# RP2350_Power.net
KiCad netlist of a schematic drawn in Altium Designer
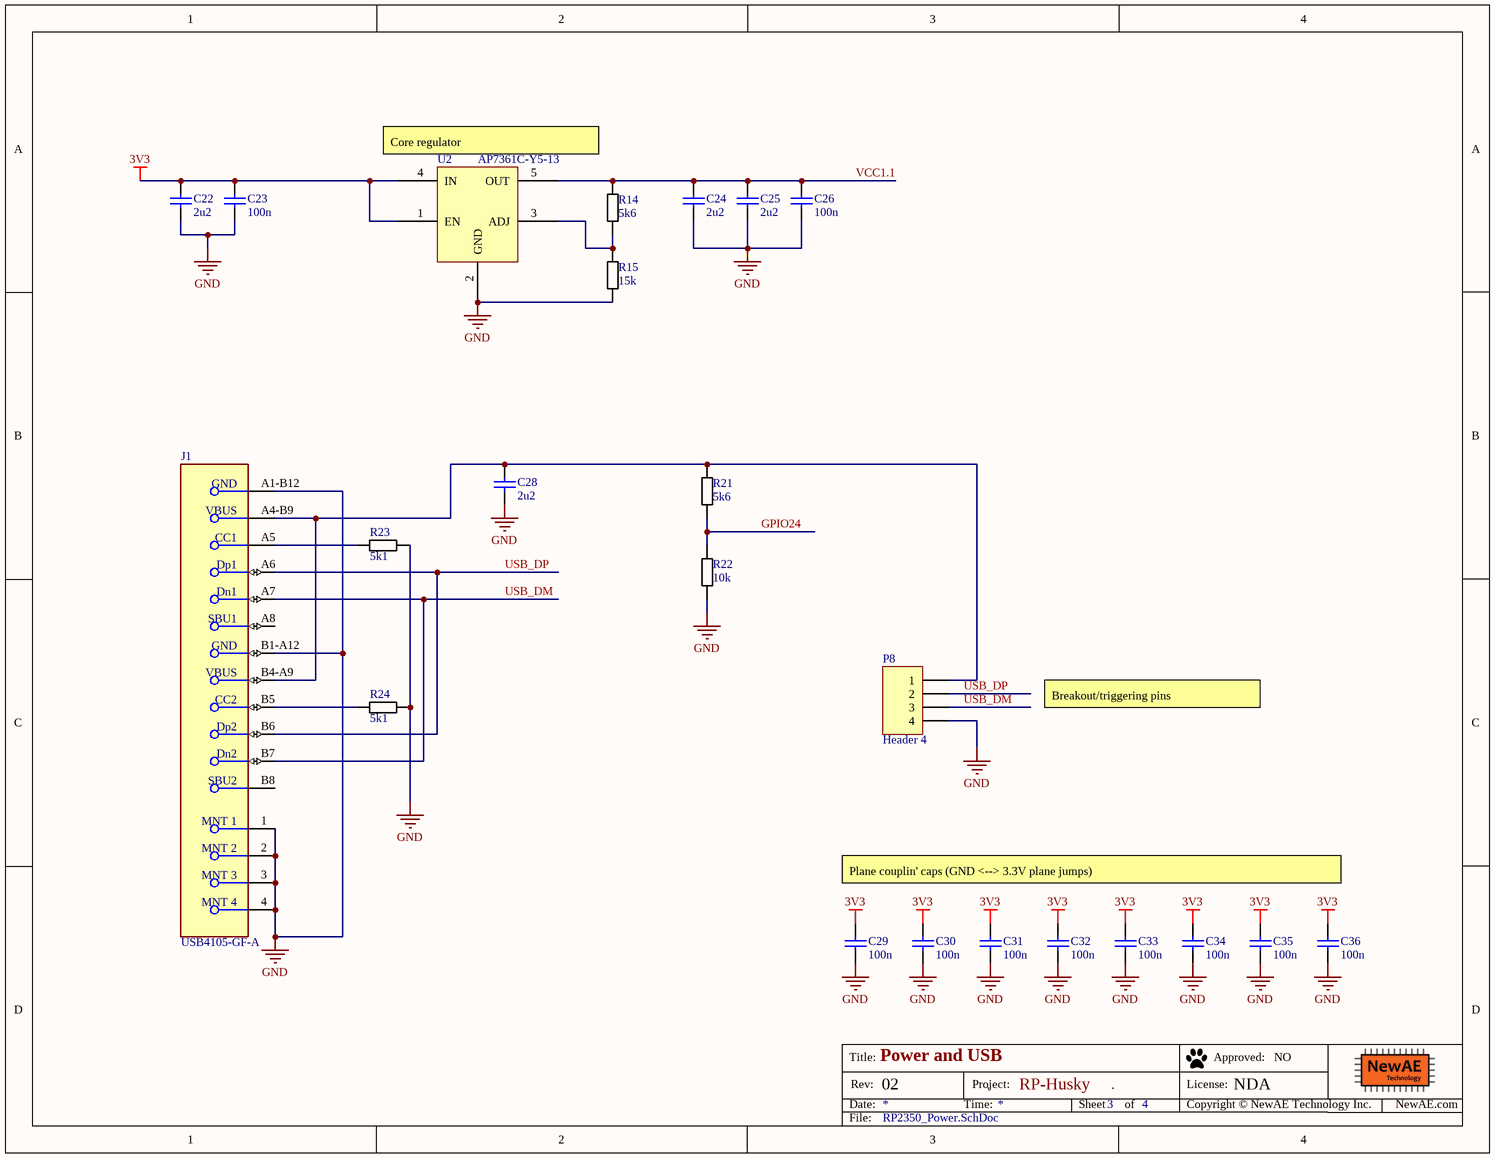
[diagram p0: RP2350_Power.SchDoc]

(export (version "E")
  (design (tool "Eeschema 10.0.6"))
  (components
    (comp (ref "C22")
      (value "2u2")
      (footprint "CAPC0603_M")
      (description "2u2, 0603")
      (fields (field (name "PART NUMBER") "CCHIP-2u2-0603"))
      (libsource (lib "NewAE_AltiumLib") (part "CAP"))
    )
    (comp (ref "C23")
      (value "100n")
      (footprint "CAPC0402_M")
      (description "100n, 0402")
      (fields (field (name "PART NUMBER") "CCHIP-100n-0402"))
      (libsource (lib "NewAE_AltiumLib") (part "CAP"))
    )
    (comp (ref "C24")
      (value "2u2")
      (footprint "CAPC0603_M")
      (description "2u2, 0603")
      (fields (field (name "PART NUMBER") "CCHIP-2u2-0603"))
      (libsource (lib "NewAE_AltiumLib") (part "CAP"))
    )
    (comp (ref "C25")
      (value "2u2")
      (footprint "CAPC0603_M")
      (description "2u2, 0603")
      (fields (field (name "PART NUMBER") "CCHIP-2u2-0603"))
      (libsource (lib "NewAE_AltiumLib") (part "CAP"))
    )
    (comp (ref "C26")
      (value "100n")
      (footprint "CAPC0402_M")
      (description "100n, 0402")
      (fields (field (name "PART NUMBER") "CCHIP-100n-0402"))
      (libsource (lib "NewAE_AltiumLib") (part "CAP"))
    )
    (comp (ref "C28")
      (value "2u2")
      (footprint "CAPC0603_M")
      (description "2u2, 0603")
      (fields (field (name "PART NUMBER") "CCHIP-2u2-0603"))
      (libsource (lib "NewAE_AltiumLib") (part "CAP"))
    )
    (comp (ref "C29")
      (value "100n")
      (footprint "CAPC0402_M")
      (description "100n, 0402")
      (fields (field (name "PART NUMBER") "CCHIP-100n-0402"))
      (libsource (lib "NewAE_AltiumLib") (part "CAP"))
    )
    (comp (ref "C30")
      (value "100n")
      (footprint "CAPC0402_M")
      (description "100n, 0402")
      (fields (field (name "PART NUMBER") "CCHIP-100n-0402"))
      (libsource (lib "NewAE_AltiumLib") (part "CAP"))
    )
    (comp (ref "C31")
      (value "100n")
      (footprint "CAPC0402_M")
      (description "100n, 0402")
      (fields (field (name "PART NUMBER") "CCHIP-100n-0402"))
      (libsource (lib "NewAE_AltiumLib") (part "CAP"))
    )
    (comp (ref "C32")
      (value "100n")
      (footprint "CAPC0402_M")
      (description "100n, 0402")
      (fields (field (name "PART NUMBER") "CCHIP-100n-0402"))
      (libsource (lib "NewAE_AltiumLib") (part "CAP"))
    )
    (comp (ref "C33")
      (value "100n")
      (footprint "CAPC0402_M")
      (description "100n, 0402")
      (fields (field (name "PART NUMBER") "CCHIP-100n-0402"))
      (libsource (lib "NewAE_AltiumLib") (part "CAP"))
    )
    (comp (ref "C34")
      (value "100n")
      (footprint "CAPC0402_M")
      (description "100n, 0402")
      (fields (field (name "PART NUMBER") "CCHIP-100n-0402"))
      (libsource (lib "NewAE_AltiumLib") (part "CAP"))
    )
    (comp (ref "C35")
      (value "100n")
      (footprint "CAPC0402_M")
      (description "100n, 0402")
      (fields (field (name "PART NUMBER") "CCHIP-100n-0402"))
      (libsource (lib "NewAE_AltiumLib") (part "CAP"))
    )
    (comp (ref "C36")
      (value "100n")
      (footprint "CAPC0402_M")
      (description "100n, 0402")
      (fields (field (name "PART NUMBER") "CCHIP-100n-0402"))
      (libsource (lib "NewAE_AltiumLib") (part "CAP"))
    )
    (comp (ref "J1")
      (value "USB4105-GF-A")
      (footprint "FP-USB4105-GF-A-MFG")
      (description "CONN RCPT USB2.0 TYPEC 5A")
      (fields
        (field (name "MANUFACTURER") "GCT")
        (field (name "OCTOPART") "https://octopart.com/usb4105-gf-a-gct-106627878")
      )
      (libsource (lib "Altium Content Vault") (part "e7c17a616881a82b79941196b4bec10"))
    )
    (comp (ref "P8")
      (value "Header 4")
      (footprint "HDR1X4")
      (description "Header, 4-Pin")
      (fields (field (name "PUBLISHER") "Altium Limited"))
      (libsource (lib "Miscellaneous Connectors") (part "Header 4"))
    )
    (comp (ref "R14")
      (value "5k6")
      (footprint "RESC1608X55N")
      (description "5k6 res, 0603, 1%, 1/10W")
      (fields (field (name "PART NUMBER") "RCHIP-5K6-0603") (field (name "TOLERANCE") "1%"))
      (libsource (lib "") (part "RES-EU_1"))
    )
    (comp (ref "R15")
      (value "15k")
      (footprint "RESC1608X55N")
      (description "15k res, 0603, 1%, 1/10W")
      (fields (field (name "PART NUMBER") "RCHIP-15K-0603") (field (name "TOLERANCE") "1%"))
      (libsource (lib "") (part "RES-EU_1"))
    )
    (comp (ref "R21")
      (value "5k6")
      (footprint "RESC1608X55N")
      (description "5k6 res, 0603, 1%, 1/10W")
      (fields (field (name "PART NUMBER") "RCHIP-5K6-0603") (field (name "TOLERANCE") "1%"))
      (libsource (lib "") (part "RES-EU_1"))
    )
    (comp (ref "R22")
      (value "10k")
      (footprint "RESC1608X55N")
      (description "10k res, 0603, 1%, 1/10W")
      (fields (field (name "PART NUMBER") "RCHIP-10K-0603") (field (name "TOLERANCE") "1%"))
      (libsource (lib "") (part "RES-EU_1"))
    )
    (comp (ref "R23")
      (value "5k1")
      (footprint "RESC1608X55N")
      (description "5k1 res, 0603, 1%, 1/10W")
      (fields (field (name "PART NUMBER") "RCHIP-5K1-0603") (field (name "TOLERANCE") "1%"))
      (libsource (lib "NewAE_AltiumLib") (part "RES-EU"))
    )
    (comp (ref "R24")
      (value "5k1")
      (footprint "RESC1608X55N")
      (description "5k1 res, 0603, 1%, 1/10W")
      (fields (field (name "PART NUMBER") "RCHIP-5K1-0603") (field (name "TOLERANCE") "1%"))
      (libsource (lib "NewAE_AltiumLib") (part "RES-EU"))
    )
    (comp (ref "U2")
      (value "AP7361C-Y5-13")
      (footprint "SOT89-5")
      (description "Regulator, Adj, LDO, 1A")
      (libsource (lib "NewAE_AltiumLib") (part "AP7361C-Y5-13"))
    )
  )
  (nets
    (net (code "1") (name "/GPIO24") (class "Default")
      (node (ref "R21") (pin "2") (pinfunction "2_2") (pintype "passive"))
      (node (ref "R22") (pin "1") (pinfunction "1_1") (pintype "passive"))
    )
    (net (code "2") (name "/USB_DM") (class "Default")
      (node (ref "J1") (pin "A7") (pinfunction "Dn1_A7") (pintype "bidirectional"))
      (node (ref "J1") (pin "B7") (pinfunction "Dn2_B7") (pintype "bidirectional"))
      (node (ref "P8") (pin "3") (pinfunction "3_3") (pintype "passive"))
    )
    (net (code "3") (name "/USB_DP") (class "Default")
      (node (ref "J1") (pin "A6") (pinfunction "Dp1_A6") (pintype "bidirectional"))
      (node (ref "J1") (pin "B6") (pinfunction "Dp2_B6") (pintype "bidirectional"))
      (node (ref "P8") (pin "2") (pinfunction "2_2") (pintype "passive"))
    )
    (net (code "4") (name "/VCC1.1") (class "Default")
      (node (ref "C24") (pin "1") (pinfunction "1_1") (pintype "passive"))
      (node (ref "C25") (pin "1") (pinfunction "1_1") (pintype "passive"))
      (node (ref "C26") (pin "1") (pinfunction "1_1") (pintype "passive"))
      (node (ref "R14") (pin "1") (pinfunction "1_1") (pintype "passive"))
      (node (ref "U2") (pin "5") (pinfunction "OUT_5") (pintype "passive"))
    )
    (net (code "5") (name "3V3") (class "Default")
      (node (ref "C22") (pin "1") (pinfunction "1_1") (pintype "passive"))
      (node (ref "C23") (pin "1") (pinfunction "1_1") (pintype "passive"))
      (node (ref "C29") (pin "1") (pinfunction "1_1") (pintype "passive"))
      (node (ref "C30") (pin "1") (pinfunction "1_1") (pintype "passive"))
      (node (ref "C31") (pin "1") (pinfunction "1_1") (pintype "passive"))
      (node (ref "C32") (pin "1") (pinfunction "1_1") (pintype "passive"))
      (node (ref "C33") (pin "1") (pinfunction "1_1") (pintype "passive"))
      (node (ref "C34") (pin "1") (pinfunction "1_1") (pintype "passive"))
      (node (ref "C35") (pin "1") (pinfunction "1_1") (pintype "passive"))
      (node (ref "C36") (pin "1") (pinfunction "1_1") (pintype "passive"))
      (node (ref "U2") (pin "1") (pinfunction "EN_1") (pintype "passive"))
      (node (ref "U2") (pin "4") (pinfunction "IN_4") (pintype "passive"))
    )
    (net (code "6") (name "GND") (class "Default")
      (node (ref "C22") (pin "2") (pinfunction "2_2") (pintype "passive"))
      (node (ref "C23") (pin "2") (pinfunction "2_2") (pintype "passive"))
      (node (ref "C24") (pin "2") (pinfunction "2_2") (pintype "passive"))
      (node (ref "C25") (pin "2") (pinfunction "2_2") (pintype "passive"))
      (node (ref "C26") (pin "2") (pinfunction "2_2") (pintype "passive"))
      (node (ref "C28") (pin "2") (pinfunction "2_2") (pintype "passive"))
      (node (ref "C29") (pin "2") (pinfunction "2_2") (pintype "passive"))
      (node (ref "C30") (pin "2") (pinfunction "2_2") (pintype "passive"))
      (node (ref "C31") (pin "2") (pinfunction "2_2") (pintype "passive"))
      (node (ref "C32") (pin "2") (pinfunction "2_2") (pintype "passive"))
      (node (ref "C33") (pin "2") (pinfunction "2_2") (pintype "passive"))
      (node (ref "C34") (pin "2") (pinfunction "2_2") (pintype "passive"))
      (node (ref "C35") (pin "2") (pinfunction "2_2") (pintype "passive"))
      (node (ref "C36") (pin "2") (pinfunction "2_2") (pintype "passive"))
      (node (ref "J1") (pin "1") (pinfunction "MNT_1_1") (pintype "power_in"))
      (node (ref "J1") (pin "2") (pinfunction "MNT_2_2") (pintype "power_in"))
      (node (ref "J1") (pin "3") (pinfunction "MNT_3_3") (pintype "power_in"))
      (node (ref "J1") (pin "4") (pinfunction "MNT_4_4") (pintype "power_in"))
      (node (ref "J1") (pin "A1-B12") (pinfunction "GND_A1-B12") (pintype "power_in"))
      (node (ref "J1") (pin "B1-A12") (pinfunction "GND_B1-A12") (pintype "bidirectional"))
      (node (ref "P8") (pin "4") (pinfunction "4_4") (pintype "passive"))
      (node (ref "R15") (pin "2") (pinfunction "2_2") (pintype "passive"))
      (node (ref "R22") (pin "2") (pinfunction "2_2") (pintype "passive"))
      (node (ref "R23") (pin "2") (pinfunction "2_2") (pintype "passive"))
      (node (ref "R24") (pin "2") (pinfunction "2_2") (pintype "passive"))
      (node (ref "U2") (pin "2") (pinfunction "GND_2") (pintype "passive"))
    )
    (net (code "7") (name "Net-(C28-Pad1)") (class "Default")
      (node (ref "C28") (pin "1") (pinfunction "1_1") (pintype "passive"))
      (node (ref "J1") (pin "A4-B9") (pinfunction "VBUS_A4-B9") (pintype "power_in"))
      (node (ref "J1") (pin "B4-A9") (pinfunction "VBUS_B4-A9") (pintype "bidirectional"))
      (node (ref "P8") (pin "1") (pinfunction "1_1") (pintype "passive"))
      (node (ref "R21") (pin "1") (pinfunction "1_1") (pintype "passive"))
    )
    (net (code "8") (name "Net-(J1-CC1)") (class "Default")
      (node (ref "J1") (pin "A5") (pinfunction "CC1_A5") (pintype "power_in"))
      (node (ref "R23") (pin "1") (pinfunction "1_1") (pintype "passive"))
    )
    (net (code "9") (name "Net-(J1-CC2)") (class "Default")
      (node (ref "J1") (pin "B5") (pinfunction "CC2_B5") (pintype "bidirectional"))
      (node (ref "R24") (pin "1") (pinfunction "1_1") (pintype "passive"))
    )
    (net (code "10") (name "Net-(U2-ADJ)") (class "Default")
      (node (ref "R14") (pin "2") (pinfunction "2_2") (pintype "passive"))
      (node (ref "R15") (pin "1") (pinfunction "1_1") (pintype "passive"))
      (node (ref "U2") (pin "3") (pinfunction "ADJ_3") (pintype "passive"))
    )
    (net (code "11") (name "unconnected-(J1-SBU1-PadA8)") (class "Default")
      (node (ref "J1") (pin "A8") (pinfunction "SBU1_A8") (pintype "bidirectional"))
    )
    (net (code "12") (name "unconnected-(J1-SBU2-PadB8)") (class "Default")
      (node (ref "J1") (pin "B8") (pinfunction "SBU2_B8") (pintype "power_in"))
    )
  )
)
